# ModemAdapter.net
KiCad netlist of a schematic drawn in EAGLE
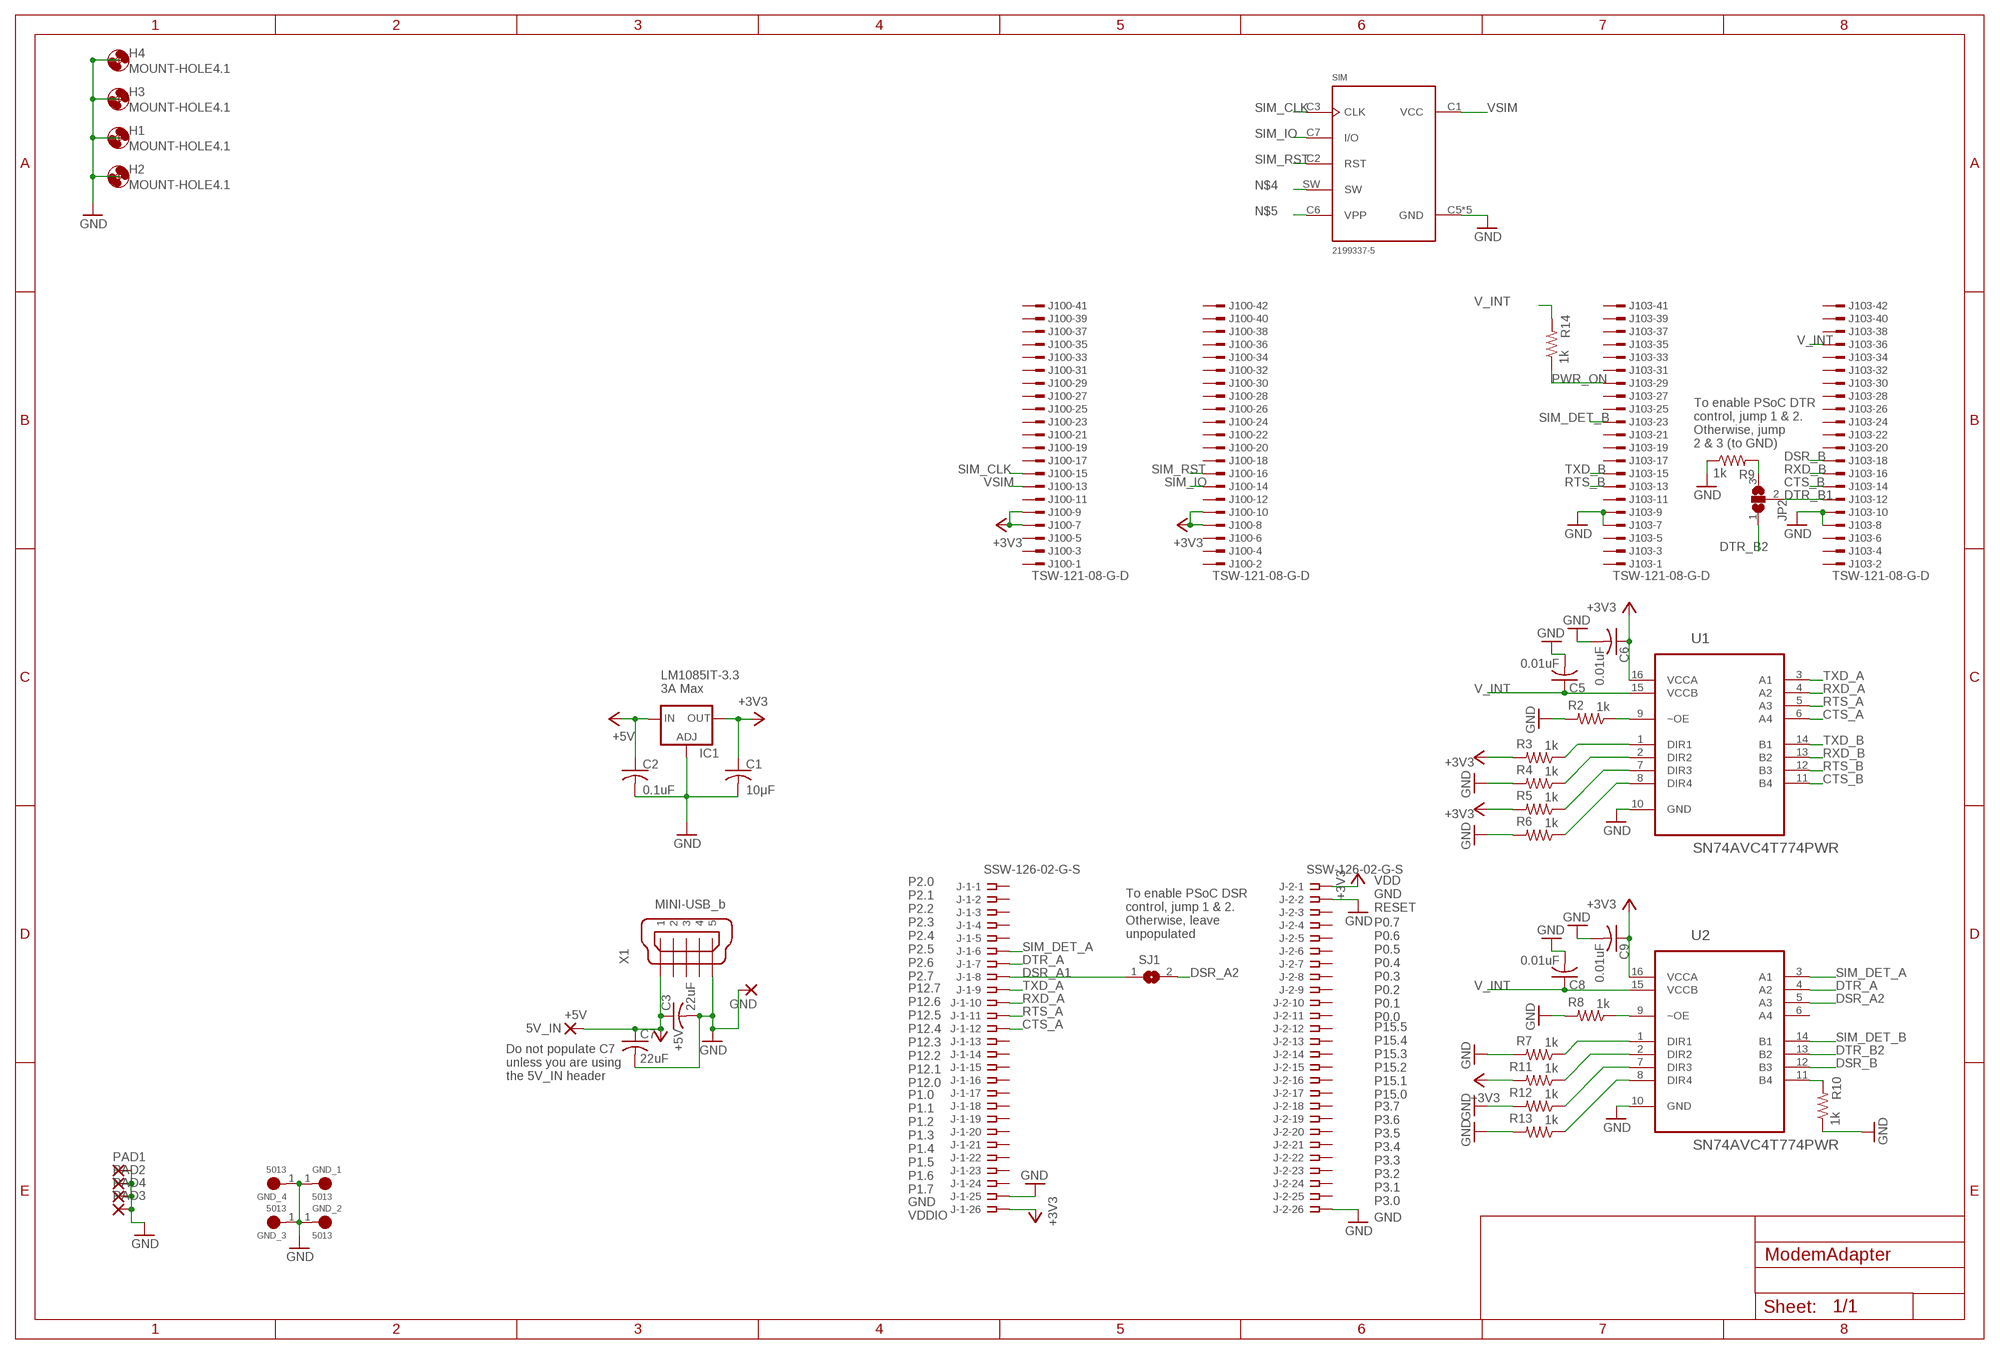
[diagram p0: schematic, sheet 1]

(export (version "E")
  (design (tool "Eeschema 10.0.6"))
  (components
    (comp (ref "+5V")
      (value "5V_IN")
      (footprint "eagle-import:3,17_1,1")
      (libsource (lib "eagle-import") (part "3,17/1,1"))
    )
    (comp (ref "C1")
      (value "10μF")
      (footprint "eagle-import:C050-024X044")
      (libsource (lib "eagle-import") (part "C-US050-024X044"))
    )
    (comp (ref "C2")
      (value "0.1uF")
      (footprint "eagle-import:C050-024X044")
      (libsource (lib "eagle-import") (part "C-US050-024X044"))
    )
    (comp (ref "C3")
      (value "22uF")
      (footprint "eagle-import:C050-024X044")
      (libsource (lib "eagle-import") (part "C-US050-024X044"))
    )
    (comp (ref "C5")
      (value "0.01uF")
      (footprint "eagle-import:C050-024X044")
      (libsource (lib "eagle-import") (part "C-US050-024X044"))
    )
    (comp (ref "C6")
      (value "0.01uF")
      (footprint "eagle-import:C050-024X044")
      (libsource (lib "eagle-import") (part "C-US050-024X044"))
    )
    (comp (ref "C7")
      (value "22uF")
      (footprint "eagle-import:C050-024X044")
      (libsource (lib "eagle-import") (part "C-US050-024X044"))
    )
    (comp (ref "C8")
      (value "0.01uF")
      (footprint "eagle-import:C050-024X044")
      (libsource (lib "eagle-import") (part "C-US050-024X044"))
    )
    (comp (ref "C9")
      (value "0.01uF")
      (footprint "eagle-import:C050-024X044")
      (libsource (lib "eagle-import") (part "C-US050-024X044"))
    )
    (comp (ref "GND")
      (value "3,17/1,1")
      (footprint "eagle-import:3,17_1,1")
      (libsource (lib "eagle-import") (part "3,17/1,1"))
    )
    (comp (ref "GND_1")
      (value "5013")
      (footprint "eagle-import:TESTPOINT_5013")
      (fields (field (name "MF") "Keystone Electronics"))
      (libsource (lib "eagle-import") (part "5013"))
    )
    (comp (ref "GND_2")
      (value "5013")
      (footprint "eagle-import:TESTPOINT_5013")
      (fields (field (name "MF") "Keystone Electronics"))
      (libsource (lib "eagle-import") (part "5013"))
    )
    (comp (ref "GND_3")
      (value "5013")
      (footprint "eagle-import:TESTPOINT_5013")
      (fields (field (name "MF") "Keystone Electronics"))
      (libsource (lib "eagle-import") (part "5013"))
    )
    (comp (ref "GND_4")
      (value "5013")
      (footprint "eagle-import:TESTPOINT_5013")
      (fields (field (name "MF") "Keystone Electronics"))
      (libsource (lib "eagle-import") (part "5013"))
    )
    (comp (ref "H1")
      (value "MOUNT-HOLE4.1")
      (footprint "eagle-import:4,1")
      (libsource (lib "eagle-import") (part "MOUNT-HOLE4.1"))
    )
    (comp (ref "H2")
      (value "MOUNT-HOLE4.1")
      (footprint "eagle-import:4,1")
      (libsource (lib "eagle-import") (part "MOUNT-HOLE4.1"))
    )
    (comp (ref "H3")
      (value "MOUNT-HOLE4.1")
      (footprint "eagle-import:4,1")
      (libsource (lib "eagle-import") (part "MOUNT-HOLE4.1"))
    )
    (comp (ref "H4")
      (value "MOUNT-HOLE4.1")
      (footprint "eagle-import:4,1")
      (libsource (lib "eagle-import") (part "MOUNT-HOLE4.1"))
    )
    (comp (ref "IC1")
      (value "LD117AV33")
      (footprint "eagle-import:TO220L1")
      (libsource (lib "eagle-import") (part "LD117A?V33"))
    )
    (comp (ref "J-1")
      (value "SSW-126-02-G-S")
      (footprint "eagle-import:SSW-126-02-G-S")
      (fields (field (name "MF") "Samtec Inc."))
      (libsource (lib "eagle-import") (part "SSW-126-02-G-S"))
    )
    (comp (ref "J-2")
      (value "SSW-126-02-G-S")
      (footprint "eagle-import:SSW-126-02-G-S")
      (fields (field (name "MF") "Samtec Inc."))
      (libsource (lib "eagle-import") (part "SSW-126-02-G-S"))
    )
    (comp (ref "J100")
      (value "TSW-121-08-G-D")
      (footprint "eagle-import:TSW-121-XX-G-D")
      (fields (field (name "MF") "Samtec Inc.") (field (name "MPN") "TSW-121-07-G-D"))
      (libsource (lib "eagle-import") (part "TSW-121--G-D08"))
    )
    (comp (ref "J103")
      (value "TSW-121-08-G-D")
      (footprint "eagle-import:TSW-121-XX-G-D")
      (fields (field (name "MF") "Samtec Inc.") (field (name "MPN") "TSW-121-07-G-D"))
      (libsource (lib "eagle-import") (part "TSW-121--G-D08"))
    )
    (comp (ref "JP2")
      (value "SJ2W")
      (footprint "eagle-import:SJ_2")
      (libsource (lib "eagle-import") (part "SJ2W"))
    )
    (comp (ref "PAD1")
      (value "SMD2")
      (footprint "eagle-import:SMD1,27-2,54")
      (libsource (lib "eagle-import") (part "SMD2"))
    )
    (comp (ref "PAD2")
      (value "SMD2")
      (footprint "eagle-import:SMD1,27-2,54")
      (libsource (lib "eagle-import") (part "SMD2"))
    )
    (comp (ref "PAD3")
      (value "SMD2")
      (footprint "eagle-import:SMD1,27-2,54")
      (libsource (lib "eagle-import") (part "SMD2"))
    )
    (comp (ref "PAD4")
      (value "SMD2")
      (footprint "eagle-import:SMD1,27-2,54")
      (libsource (lib "eagle-import") (part "SMD2"))
    )
    (comp (ref "R2")
      (value "1k")
      (footprint "eagle-import:0204_7")
      (libsource (lib "eagle-import") (part "R-US_0204/7"))
    )
    (comp (ref "R3")
      (value "1k")
      (footprint "eagle-import:0204_7")
      (libsource (lib "eagle-import") (part "R-US_0204/7"))
    )
    (comp (ref "R4")
      (value "1k")
      (footprint "eagle-import:0204_7")
      (libsource (lib "eagle-import") (part "R-US_0204/7"))
    )
    (comp (ref "R5")
      (value "1k")
      (footprint "eagle-import:0204_7")
      (libsource (lib "eagle-import") (part "R-US_0204/7"))
    )
    (comp (ref "R6")
      (value "1k")
      (footprint "eagle-import:0204_7")
      (libsource (lib "eagle-import") (part "R-US_0204/7"))
    )
    (comp (ref "R7")
      (value "1k")
      (footprint "eagle-import:0204_7")
      (libsource (lib "eagle-import") (part "R-US_0204/7"))
    )
    (comp (ref "R8")
      (value "1k")
      (footprint "eagle-import:0204_7")
      (libsource (lib "eagle-import") (part "R-US_0204/7"))
    )
    (comp (ref "R9")
      (value "1k")
      (footprint "eagle-import:0204_7")
      (libsource (lib "eagle-import") (part "R-US_0204/7"))
    )
    (comp (ref "R10")
      (value "1k")
      (footprint "eagle-import:0204_7")
      (libsource (lib "eagle-import") (part "R-US_0204/7"))
    )
    (comp (ref "R11")
      (value "1k")
      (footprint "eagle-import:0204_7")
      (libsource (lib "eagle-import") (part "R-US_0204/7"))
    )
    (comp (ref "R12")
      (value "1k")
      (footprint "eagle-import:0204_7")
      (libsource (lib "eagle-import") (part "R-US_0204/7"))
    )
    (comp (ref "R13")
      (value "1k")
      (footprint "eagle-import:0204_7")
      (libsource (lib "eagle-import") (part "R-US_0204/7"))
    )
    (comp (ref "R14")
      (value "1k")
      (footprint "eagle-import:0204_7")
      (libsource (lib "eagle-import") (part "R-US_0204/7"))
    )
    (comp (ref "SIM")
      (value "2199337-5")
      (footprint "eagle-import:TE_2199337-5")
      (fields (field (name "DIGI-KEY_PART_NUMBER") "A125065CT-ND") (field (name "MF") "TE Connectivity"))
      (libsource (lib "eagle-import") (part "2199337-5"))
    )
    (comp (ref "SJ1") (value "SJ") (footprint "eagle-import:SJ") (libsource (lib "eagle-import") (part "SJ")))
    (comp (ref "U1")
      (value "SN74AVC4T774PWR")
      (footprint "eagle-import:SOP65P640X120-16N")
      (fields (field (name "DIGI-KEY_PART_NUMBER") "296-24739-1-ND") (field (name "MF") "Texas Instruments"))
      (libsource (lib "eagle-import") (part "SN74AVC4T774PWR"))
    )
    (comp (ref "U2")
      (value "SN74AVC4T774PWR")
      (footprint "eagle-import:SOP65P640X120-16N")
      (fields (field (name "DIGI-KEY_PART_NUMBER") "296-24739-1-ND") (field (name "MF") "Texas Instruments"))
      (libsource (lib "eagle-import") (part "SN74AVC4T774PWR"))
    )
    (comp (ref "X1")
      (value "MINI-USB_b")
      (footprint "eagle-import:32005-601")
      (libsource (lib "eagle-import") (part "MINI-USB_SHIELD5P2-32005-601"))
    )
  )
  (nets
    (net (code "1") (name "+3V3") (class "Default")
      (node (ref "C1") (pin "1") (pinfunction "1_1") (pintype "passive"))
      (node (ref "C6") (pin "1") (pinfunction "1_1") (pintype "passive"))
      (node (ref "C9") (pin "1") (pinfunction "1_1") (pintype "passive"))
      (node (ref "IC1") (pin "2") (pinfunction "OUT_2") (pintype "passive"))
      (node (ref "J-1") (pin "26") (pinfunction "1_26") (pintype "passive"))
      (node (ref "J-2") (pin "1") (pinfunction "1_1") (pintype "passive"))
      (node (ref "J100") (pin "10") (pinfunction "1_10") (pintype "passive"))
      (node (ref "J100") (pin "7") (pinfunction "1_7") (pintype "passive"))
      (node (ref "J100") (pin "8") (pinfunction "1_8") (pintype "passive"))
      (node (ref "J100") (pin "9") (pinfunction "1_9") (pintype "passive"))
      (node (ref "R11") (pin "2") (pinfunction "2_2") (pintype "passive"))
      (node (ref "R3") (pin "2") (pinfunction "2_2") (pintype "passive"))
      (node (ref "R5") (pin "2") (pinfunction "2_2") (pintype "passive"))
      (node (ref "U1") (pin "16") (pinfunction "VCCA_16") (pintype "power_in"))
      (node (ref "U2") (pin "16") (pinfunction "VCCA_16") (pintype "power_in"))
    )
    (net (code "2") (name "+5V") (class "Default")
      (node (ref "+5V") (pin "1") (pinfunction "P_1") (pintype "passive"))
      (node (ref "C2") (pin "1") (pinfunction "1_1") (pintype "passive"))
      (node (ref "C3") (pin "1") (pinfunction "1_1") (pintype "passive"))
      (node (ref "C7") (pin "1") (pinfunction "1_1") (pintype "passive"))
      (node (ref "IC1") (pin "3") (pinfunction "IN_3") (pintype "input"))
      (node (ref "X1") (pin "1") (pinfunction "1_1") (pintype "passive"))
    )
    (net (code "3") (name "/CTS_A") (class "Default")
      (node (ref "J-1") (pin "12") (pinfunction "1_12") (pintype "passive"))
      (node (ref "U1") (pin "6") (pinfunction "A4_6") (pintype "bidirectional"))
    )
    (net (code "4") (name "/CTS_B") (class "Default")
      (node (ref "J103") (pin "14") (pinfunction "1_14") (pintype "passive"))
      (node (ref "U1") (pin "11") (pinfunction "B4_11") (pintype "bidirectional"))
    )
    (net (code "5") (name "/DSR_A1") (class "Default")
      (node (ref "J-1") (pin "8") (pinfunction "1_8") (pintype "passive"))
      (node (ref "SJ1") (pin "1") (pinfunction "1_1") (pintype "passive"))
    )
    (net (code "6") (name "/DSR_A2") (class "Default")
      (node (ref "SJ1") (pin "2") (pinfunction "2_2") (pintype "passive"))
      (node (ref "U2") (pin "5") (pinfunction "A3_5") (pintype "bidirectional"))
    )
    (net (code "7") (name "/DSR_B") (class "Default")
      (node (ref "J103") (pin "18") (pinfunction "1_18") (pintype "passive"))
      (node (ref "U2") (pin "12") (pinfunction "B3_12") (pintype "bidirectional"))
    )
    (net (code "8") (name "/DTR_A") (class "Default")
      (node (ref "J-1") (pin "7") (pinfunction "1_7") (pintype "passive"))
      (node (ref "U2") (pin "4") (pinfunction "A2_4") (pintype "bidirectional"))
    )
    (net (code "9") (name "/DTR_B1") (class "Default")
      (node (ref "J103") (pin "12") (pinfunction "1_12") (pintype "passive"))
      (node (ref "JP2") (pin "2") (pinfunction "2_2") (pintype "passive"))
    )
    (net (code "10") (name "/DTR_B2") (class "Default")
      (node (ref "JP2") (pin "1") (pinfunction "1_1") (pintype "passive"))
      (node (ref "U2") (pin "13") (pinfunction "B2_13") (pintype "bidirectional"))
    )
    (net (code "11") (name "/N$4") (class "Default")
      (node (ref "SIM") (pin "SW") (pinfunction "SW_SW") (pintype "passive"))
    )
    (net (code "12") (name "/N$5") (class "Default")
      (node (ref "SIM") (pin "C6") (pinfunction "VPP_C6") (pintype "passive"))
    )
    (net (code "13") (name "/PWR_ON") (class "Default")
      (node (ref "J103") (pin "29") (pinfunction "1_29") (pintype "passive"))
      (node (ref "R14") (pin "1") (pinfunction "1_1") (pintype "passive"))
    )
    (net (code "14") (name "/RTS_A") (class "Default")
      (node (ref "J-1") (pin "11") (pinfunction "1_11") (pintype "passive"))
      (node (ref "U1") (pin "5") (pinfunction "A3_5") (pintype "bidirectional"))
    )
    (net (code "15") (name "/RTS_B") (class "Default")
      (node (ref "J103") (pin "13") (pinfunction "1_13") (pintype "passive"))
      (node (ref "U1") (pin "12") (pinfunction "B3_12") (pintype "bidirectional"))
    )
    (net (code "16") (name "/RXD_A") (class "Default")
      (node (ref "J-1") (pin "10") (pinfunction "1_10") (pintype "passive"))
      (node (ref "U1") (pin "4") (pinfunction "A2_4") (pintype "bidirectional"))
    )
    (net (code "17") (name "/RXD_B") (class "Default")
      (node (ref "J103") (pin "16") (pinfunction "1_16") (pintype "passive"))
      (node (ref "U1") (pin "13") (pinfunction "B2_13") (pintype "bidirectional"))
    )
    (net (code "18") (name "/SIM_CLK") (class "Default")
      (node (ref "J100") (pin "15") (pinfunction "1_15") (pintype "passive"))
      (node (ref "SIM") (pin "C3") (pinfunction "CLK_C3") (pintype "input"))
    )
    (net (code "19") (name "/SIM_DET_A") (class "Default")
      (node (ref "J-1") (pin "6") (pinfunction "1_6") (pintype "passive"))
      (node (ref "U2") (pin "3") (pinfunction "A1_3") (pintype "bidirectional"))
    )
    (net (code "20") (name "/SIM_DET_B") (class "Default")
      (node (ref "J103") (pin "23") (pinfunction "1_23") (pintype "passive"))
      (node (ref "U2") (pin "14") (pinfunction "B1_14") (pintype "bidirectional"))
    )
    (net (code "21") (name "/SIM_IO") (class "Default")
      (node (ref "J100") (pin "14") (pinfunction "1_14") (pintype "passive"))
      (node (ref "SIM") (pin "C7") (pinfunction "I/O_C7") (pintype "bidirectional"))
    )
    (net (code "22") (name "/SIM_RST") (class "Default")
      (node (ref "J100") (pin "16") (pinfunction "1_16") (pintype "passive"))
      (node (ref "SIM") (pin "C2") (pinfunction "RST_C2") (pintype "passive"))
    )
    (net (code "23") (name "/TXD_A") (class "Default")
      (node (ref "J-1") (pin "9") (pinfunction "1_9") (pintype "passive"))
      (node (ref "U1") (pin "3") (pinfunction "A1_3") (pintype "bidirectional"))
    )
    (net (code "24") (name "/TXD_B") (class "Default")
      (node (ref "J103") (pin "15") (pinfunction "1_15") (pintype "passive"))
      (node (ref "U1") (pin "14") (pinfunction "B1_14") (pintype "bidirectional"))
    )
    (net (code "25") (name "/VSIM") (class "Default")
      (node (ref "J100") (pin "13") (pinfunction "1_13") (pintype "passive"))
      (node (ref "SIM") (pin "C1") (pinfunction "VCC_C1") (pintype "power_in"))
    )
    (net (code "26") (name "/V_INT") (class "Default")
      (node (ref "C5") (pin "1") (pinfunction "1_1") (pintype "passive"))
      (node (ref "C8") (pin "1") (pinfunction "1_1") (pintype "passive"))
      (node (ref "J103") (pin "36") (pinfunction "1_36") (pintype "passive"))
      (node (ref "R14") (pin "2") (pinfunction "2_2") (pintype "passive"))
      (node (ref "U1") (pin "15") (pinfunction "VCCB_15") (pintype "power_in"))
      (node (ref "U2") (pin "15") (pinfunction "VCCB_15") (pintype "power_in"))
    )
    (net (code "27") (name "GND") (class "Default")
      (node (ref "C1") (pin "2") (pinfunction "2_2") (pintype "passive"))
      (node (ref "C2") (pin "2") (pinfunction "2_2") (pintype "passive"))
      (node (ref "C3") (pin "2") (pinfunction "2_2") (pintype "passive"))
      (node (ref "C5") (pin "2") (pinfunction "2_2") (pintype "passive"))
      (node (ref "C6") (pin "2") (pinfunction "2_2") (pintype "passive"))
      (node (ref "C7") (pin "2") (pinfunction "2_2") (pintype "passive"))
      (node (ref "C8") (pin "2") (pinfunction "2_2") (pintype "passive"))
      (node (ref "C9") (pin "2") (pinfunction "2_2") (pintype "passive"))
      (node (ref "GND") (pin "1") (pinfunction "P_1") (pintype "passive"))
      (node (ref "GND_1") (pin "1") (pinfunction "TP_1") (pintype "passive"))
      (node (ref "GND_2") (pin "1") (pinfunction "TP_1") (pintype "passive"))
      (node (ref "GND_3") (pin "1") (pinfunction "TP_1") (pintype "passive"))
      (node (ref "GND_4") (pin "1") (pinfunction "TP_1") (pintype "passive"))
      (node (ref "IC1") (pin "1") (pinfunction "ADJ_1") (pintype "input"))
      (node (ref "J-1") (pin "25") (pinfunction "1_25") (pintype "passive"))
      (node (ref "J-2") (pin "2") (pinfunction "1_2") (pintype "passive"))
      (node (ref "J-2") (pin "26") (pinfunction "1_26") (pintype "passive"))
      (node (ref "J103") (pin "10") (pinfunction "1_10") (pintype "passive"))
      (node (ref "J103") (pin "7") (pinfunction "1_7") (pintype "passive"))
      (node (ref "J103") (pin "8") (pinfunction "1_8") (pintype "passive"))
      (node (ref "J103") (pin "9") (pinfunction "1_9") (pintype "passive"))
      (node (ref "PAD1") (pin "1") (pinfunction "P_1") (pintype "passive"))
      (node (ref "PAD2") (pin "1") (pinfunction "P_1") (pintype "passive"))
      (node (ref "PAD3") (pin "1") (pinfunction "P_1") (pintype "passive"))
      (node (ref "PAD4") (pin "1") (pinfunction "P_1") (pintype "passive"))
      (node (ref "R10") (pin "1") (pinfunction "1_1") (pintype "passive"))
      (node (ref "R12") (pin "2") (pinfunction "2_2") (pintype "passive"))
      (node (ref "R13") (pin "2") (pinfunction "2_2") (pintype "passive"))
      (node (ref "R2") (pin "2") (pinfunction "2_2") (pintype "passive"))
      (node (ref "R4") (pin "2") (pinfunction "2_2") (pintype "passive"))
      (node (ref "R6") (pin "2") (pinfunction "2_2") (pintype "passive"))
      (node (ref "R7") (pin "2") (pinfunction "2_2") (pintype "passive"))
      (node (ref "R8") (pin "2") (pinfunction "2_2") (pintype "passive"))
      (node (ref "R9") (pin "1") (pinfunction "1_1") (pintype "passive"))
      (node (ref "SIM") (pin "C5") (pinfunction "GND_C5") (pintype "power_in"))
      (node (ref "SIM") (pin "G1") (pinfunction "GND_G1") (pintype "power_in"))
      (node (ref "SIM") (pin "G2") (pinfunction "GND_G2") (pintype "power_in"))
      (node (ref "SIM") (pin "G3") (pinfunction "GND_G3") (pintype "power_in"))
      (node (ref "SIM") (pin "G4") (pinfunction "GND_G4") (pintype "power_in"))
      (node (ref "U1") (pin "10") (pinfunction "GND_10") (pintype "passive"))
      (node (ref "U2") (pin "10") (pinfunction "GND_10") (pintype "passive"))
      (node (ref "X1") (pin "5") (pinfunction "5_5") (pintype "passive"))
    )
    (net (code "28") (name "Net-(JP2-Pad3)") (class "Default")
      (node (ref "JP2") (pin "3") (pinfunction "3_3") (pintype "passive"))
      (node (ref "R9") (pin "2") (pinfunction "2_2") (pintype "passive"))
    )
    (net (code "29") (name "Net-(U1-DIR1)") (class "Default")
      (node (ref "R3") (pin "1") (pinfunction "1_1") (pintype "passive"))
      (node (ref "U1") (pin "1") (pinfunction "DIR1_1") (pintype "input"))
    )
    (net (code "30") (name "Net-(U1-DIR2)") (class "Default")
      (node (ref "R4") (pin "1") (pinfunction "1_1") (pintype "passive"))
      (node (ref "U1") (pin "2") (pinfunction "DIR2_2") (pintype "input"))
    )
    (net (code "31") (name "Net-(U1-DIR3)") (class "Default")
      (node (ref "R5") (pin "1") (pinfunction "1_1") (pintype "passive"))
      (node (ref "U1") (pin "7") (pinfunction "DIR3_7") (pintype "input"))
    )
    (net (code "32") (name "Net-(U1-DIR4)") (class "Default")
      (node (ref "R6") (pin "1") (pinfunction "1_1") (pintype "passive"))
      (node (ref "U1") (pin "8") (pinfunction "DIR4_8") (pintype "input"))
    )
    (net (code "33") (name "Net-(U1-~{OE})") (class "Default")
      (node (ref "R2") (pin "1") (pinfunction "1_1") (pintype "passive"))
      (node (ref "U1") (pin "9") (pinfunction "~{OE}_9") (pintype "input"))
    )
    (net (code "34") (name "Net-(U2-B4)") (class "Default")
      (node (ref "R10") (pin "2") (pinfunction "2_2") (pintype "passive"))
      (node (ref "U2") (pin "11") (pinfunction "B4_11") (pintype "bidirectional"))
    )
    (net (code "35") (name "Net-(U2-DIR1)") (class "Default")
      (node (ref "R7") (pin "1") (pinfunction "1_1") (pintype "passive"))
      (node (ref "U2") (pin "1") (pinfunction "DIR1_1") (pintype "input"))
    )
    (net (code "36") (name "Net-(U2-DIR2)") (class "Default")
      (node (ref "R11") (pin "1") (pinfunction "1_1") (pintype "passive"))
      (node (ref "U2") (pin "2") (pinfunction "DIR2_2") (pintype "input"))
    )
    (net (code "37") (name "Net-(U2-DIR3)") (class "Default")
      (node (ref "R12") (pin "1") (pinfunction "1_1") (pintype "passive"))
      (node (ref "U2") (pin "7") (pinfunction "DIR3_7") (pintype "input"))
    )
    (net (code "38") (name "Net-(U2-DIR4)") (class "Default")
      (node (ref "R13") (pin "1") (pinfunction "1_1") (pintype "passive"))
      (node (ref "U2") (pin "8") (pinfunction "DIR4_8") (pintype "input"))
    )
    (net (code "39") (name "Net-(U2-~{OE})") (class "Default")
      (node (ref "R8") (pin "1") (pinfunction "1_1") (pintype "passive"))
      (node (ref "U2") (pin "9") (pinfunction "~{OE}_9") (pintype "input"))
    )
    (net (code "40") (name "unconnected-(J-1-Pad1)") (class "Default")
      (node (ref "J-1") (pin "1") (pinfunction "1_1") (pintype "passive"))
    )
    (net (code "41") (name "unconnected-(J-1E-1-Pad13)") (class "Default")
      (node (ref "J-1") (pin "13") (pinfunction "1_13") (pintype "passive"))
    )
    (net (code "42") (name "unconnected-(J-1F-1-Pad14)") (class "Default")
      (node (ref "J-1") (pin "14") (pinfunction "1_14") (pintype "passive"))
    )
    (net (code "43") (name "unconnected-(J-1G-1-Pad15)") (class "Default")
      (node (ref "J-1") (pin "15") (pinfunction "1_15") (pintype "passive"))
    )
    (net (code "44") (name "unconnected-(J-1H-1-Pad16)") (class "Default")
      (node (ref "J-1") (pin "16") (pinfunction "1_16") (pintype "passive"))
    )
    (net (code "45") (name "unconnected-(J-1I-1-Pad17)") (class "Default")
      (node (ref "J-1") (pin "17") (pinfunction "1_17") (pintype "passive"))
    )
    (net (code "46") (name "unconnected-(J-1J-1-Pad18)") (class "Default")
      (node (ref "J-1") (pin "18") (pinfunction "1_18") (pintype "passive"))
    )
    (net (code "47") (name "unconnected-(J-1K-1-Pad19)") (class "Default")
      (node (ref "J-1") (pin "19") (pinfunction "1_19") (pintype "passive"))
    )
    (net (code "48") (name "unconnected-(J-1L-1-Pad2)") (class "Default")
      (node (ref "J-1") (pin "2") (pinfunction "1_2") (pintype "passive"))
    )
    (net (code "49") (name "unconnected-(J-1M-1-Pad20)") (class "Default")
      (node (ref "J-1") (pin "20") (pinfunction "1_20") (pintype "passive"))
    )
    (net (code "50") (name "unconnected-(J-1N-1-Pad21)") (class "Default")
      (node (ref "J-1") (pin "21") (pinfunction "1_21") (pintype "passive"))
    )
    (net (code "51") (name "unconnected-(J-1O-1-Pad22)") (class "Default")
      (node (ref "J-1") (pin "22") (pinfunction "1_22") (pintype "passive"))
    )
    (net (code "52") (name "unconnected-(J-1P-1-Pad23)") (class "Default")
      (node (ref "J-1") (pin "23") (pinfunction "1_23") (pintype "passive"))
    )
    (net (code "53") (name "unconnected-(J-1Q-1-Pad24)") (class "Default")
      (node (ref "J-1") (pin "24") (pinfunction "1_24") (pintype "passive"))
    )
    (net (code "54") (name "unconnected-(J-1T-1-Pad3)") (class "Default")
      (node (ref "J-1") (pin "3") (pinfunction "1_3") (pintype "passive"))
    )
    (net (code "55") (name "unconnected-(J-1U-1-Pad4)") (class "Default")
      (node (ref "J-1") (pin "4") (pinfunction "1_4") (pintype "passive"))
    )
    (net (code "56") (name "unconnected-(J-1V-1-Pad5)") (class "Default")
      (node (ref "J-1") (pin "5") (pinfunction "1_5") (pintype "passive"))
    )
    (net (code "57") (name "unconnected-(J-2B-1-Pad10)") (class "Default")
      (node (ref "J-2") (pin "10") (pinfunction "1_10") (pintype "passive"))
    )
    (net (code "58") (name "unconnected-(J-2C-1-Pad11)") (class "Default")
      (node (ref "J-2") (pin "11") (pinfunction "1_11") (pintype "passive"))
    )
    (net (code "59") (name "unconnected-(J-2D-1-Pad12)") (class "Default")
      (node (ref "J-2") (pin "12") (pinfunction "1_12") (pintype "passive"))
    )
    (net (code "60") (name "unconnected-(J-2E-1-Pad13)") (class "Default")
      (node (ref "J-2") (pin "13") (pinfunction "1_13") (pintype "passive"))
    )
    (net (code "61") (name "unconnected-(J-2F-1-Pad14)") (class "Default")
      (node (ref "J-2") (pin "14") (pinfunction "1_14") (pintype "passive"))
    )
    (net (code "62") (name "unconnected-(J-2G-1-Pad15)") (class "Default")
      (node (ref "J-2") (pin "15") (pinfunction "1_15") (pintype "passive"))
    )
    (net (code "63") (name "unconnected-(J-2H-1-Pad16)") (class "Default")
      (node (ref "J-2") (pin "16") (pinfunction "1_16") (pintype "passive"))
    )
    (net (code "64") (name "unconnected-(J-2I-1-Pad17)") (class "Default")
      (node (ref "J-2") (pin "17") (pinfunction "1_17") (pintype "passive"))
    )
    (net (code "65") (name "unconnected-(J-2J-1-Pad18)") (class "Default")
      (node (ref "J-2") (pin "18") (pinfunction "1_18") (pintype "passive"))
    )
    (net (code "66") (name "unconnected-(J-2K-1-Pad19)") (class "Default")
      (node (ref "J-2") (pin "19") (pinfunction "1_19") (pintype "passive"))
    )
    (net (code "67") (name "unconnected-(J-2M-1-Pad20)") (class "Default")
      (node (ref "J-2") (pin "20") (pinfunction "1_20") (pintype "passive"))
    )
    (net (code "68") (name "unconnected-(J-2N-1-Pad21)") (class "Default")
      (node (ref "J-2") (pin "21") (pinfunction "1_21") (pintype "passive"))
    )
    (net (code "69") (name "unconnected-(J-2O-1-Pad22)") (class "Default")
      (node (ref "J-2") (pin "22") (pinfunction "1_22") (pintype "passive"))
    )
    (net (code "70") (name "unconnected-(J-2P-1-Pad23)") (class "Default")
      (node (ref "J-2") (pin "23") (pinfunction "1_23") (pintype "passive"))
    )
    (net (code "71") (name "unconnected-(J-2Q-1-Pad24)") (class "Default")
      (node (ref "J-2") (pin "24") (pinfunction "1_24") (pintype "passive"))
    )
    (net (code "72") (name "unconnected-(J-2R-1-Pad25)") (class "Default")
      (node (ref "J-2") (pin "25") (pinfunction "1_25") (pintype "passive"))
    )
    (net (code "73") (name "unconnected-(J-2T-1-Pad3)") (class "Default")
      (node (ref "J-2") (pin "3") (pinfunction "1_3") (pintype "passive"))
    )
    (net (code "74") (name "unconnected-(J-2U-1-Pad4)") (class "Default")
      (node (ref "J-2") (pin "4") (pinfunction "1_4") (pintype "passive"))
    )
    (net (code "75") (name "unconnected-(J-2V-1-Pad5)") (class "Default")
      (node (ref "J-2") (pin "5") (pinfunction "1_5") (pintype "passive"))
    )
    (net (code "76") (name "unconnected-(J-2W-1-Pad6)") (class "Default")
      (node (ref "J-2") (pin "6") (pinfunction "1_6") (pintype "passive"))
    )
    (net (code "77") (name "unconnected-(J-2X-1-Pad7)") (class "Default")
      (node (ref "J-2") (pin "7") (pinfunction "1_7") (pintype "passive"))
    )
    (net (code "78") (name "unconnected-(J-2Y-1-Pad8)") (class "Default")
      (node (ref "J-2") (pin "8") (pinfunction "1_8") (pintype "passive"))
    )
    (net (code "79") (name "unconnected-(J-2Z-1-Pad9)") (class "Default")
      (node (ref "J-2") (pin "9") (pinfunction "1_9") (pintype "passive"))
    )
    (net (code "80") (name "unconnected-(J100-Pad1)") (class "Default")
      (node (ref "J100") (pin "1") (pinfunction "1_1") (pintype "passive"))
    )
    (net (code "81") (name "unconnected-(J100AA-1-Pad33)") (class "Default")
      (node (ref "J100") (pin "33") (pinfunction "1_33") (pintype "passive"))
    )
    (net (code "82") (name "unconnected-(J100AB-1-Pad34)") (class "Default")
      (node (ref "J100") (pin "34") (pinfunction "1_34") (pintype "passive"))
    )
    (net (code "83") (name "unconnected-(J100AC-1-Pad35)") (class "Default")
      (node (ref "J100") (pin "35") (pinfunction "1_35") (pintype "passive"))
    )
    (net (code "84") (name "unconnected-(J100AD-1-Pad36)") (class "Default")
      (node (ref "J100") (pin "36") (pinfunction "1_36") (pintype "passive"))
    )
    (net (code "85") (name "unconnected-(J100AE-1-Pad37)") (class "Default")
      (node (ref "J100") (pin "37") (pinfunction "1_37") (pintype "passive"))
    )
    (net (code "86") (name "unconnected-(J100AF-1-Pad38)") (class "Default")
      (node (ref "J100") (pin "38") (pinfunction "1_38") (pintype "passive"))
    )
    (net (code "87") (name "unconnected-(J100AG-1-Pad39)") (class "Default")
      (node (ref "J100") (pin "39") (pinfunction "1_39") (pintype "passive"))
    )
    (net (code "88") (name "unconnected-(J100AH-1-Pad4)") (class "Default")
      (node (ref "J100") (pin "4") (pinfunction "1_4") (pintype "passive"))
    )
    (net (code "89") (name "unconnected-(J100AI-1-Pad40)") (class "Default")
      (node (ref "J100") (pin "40") (pinfunction "1_40") (pintype "passive"))
    )
    (net (code "90") (name "unconnected-(J100AJ-1-Pad41)") (class "Default")
      (node (ref "J100") (pin "41") (pinfunction "1_41") (pintype "passive"))
    )
    (net (code "91") (name "unconnected-(J100AK-1-Pad42)") (class "Default")
      (node (ref "J100") (pin "42") (pinfunction "1_42") (pintype "passive"))
    )
    (net (code "92") (name "unconnected-(J100AL-1-Pad5)") (class "Default")
      (node (ref "J100") (pin "5") (pinfunction "1_5") (pintype "passive"))
    )
    (net (code "93") (name "unconnected-(J100AM-1-Pad6)") (class "Default")
      (node (ref "J100") (pin "6") (pinfunction "1_6") (pintype "passive"))
    )
    (net (code "94") (name "unconnected-(J100C-1-Pad11)") (class "Default")
      (node (ref "J100") (pin "11") (pinfunction "1_11") (pintype "passive"))
    )
    (net (code "95") (name "unconnected-(J100D-1-Pad12)") (class "Default")
      (node (ref "J100") (pin "12") (pinfunction "1_12") (pintype "passive"))
    )
    (net (code "96") (name "unconnected-(J100I-1-Pad17)") (class "Default")
      (node (ref "J100") (pin "17") (pinfunction "1_17") (pintype "passive"))
    )
    (net (code "97") (name "unconnected-(J100J-1-Pad18)") (class "Default")
      (node (ref "J100") (pin "18") (pinfunction "1_18") (pintype "passive"))
    )
    (net (code "98") (name "unconnected-(J100K-1-Pad19)") (class "Default")
      (node (ref "J100") (pin "19") (pinfunction "1_19") (pintype "passive"))
    )
    (net (code "99") (name "unconnected-(J100L-1-Pad2)") (class "Default")
      (node (ref "J100") (pin "2") (pinfunction "1_2") (pintype "passive"))
    )
    (net (code "100") (name "unconnected-(J100M-1-Pad20)") (class "Default")
      (node (ref "J100") (pin "20") (pinfunction "1_20") (pintype "passive"))
    )
    (net (code "101") (name "unconnected-(J100N-1-Pad21)") (class "Default")
      (node (ref "J100") (pin "21") (pinfunction "1_21") (pintype "passive"))
    )
    (net (code "102") (name "unconnected-(J100O-1-Pad22)") (class "Default")
      (node (ref "J100") (pin "22") (pinfunction "1_22") (pintype "passive"))
    )
    (net (code "103") (name "unconnected-(J100P-1-Pad23)") (class "Default")
      (node (ref "J100") (pin "23") (pinfunction "1_23") (pintype "passive"))
    )
    (net (code "104") (name "unconnected-(J100Q-1-Pad24)") (class "Default")
      (node (ref "J100") (pin "24") (pinfunction "1_24") (pintype "passive"))
    )
    (net (code "105") (name "unconnected-(J100R-1-Pad25)") (class "Default")
      (node (ref "J100") (pin "25") (pinfunction "1_25") (pintype "passive"))
    )
    (net (code "106") (name "unconnected-(J100S-1-Pad26)") (class "Default")
      (node (ref "J100") (pin "26") (pinfunction "1_26") (pintype "passive"))
    )
    (net (code "107") (name "unconnected-(J100T-1-Pad27)") (class "Default")
      (node (ref "J100") (pin "27") (pinfunction "1_27") (pintype "passive"))
    )
    (net (code "108") (name "unconnected-(J100U-1-Pad28)") (class "Default")
      (node (ref "J100") (pin "28") (pinfunction "1_28") (pintype "passive"))
    )
    (net (code "109") (name "unconnected-(J100V-1-Pad29)") (class "Default")
      (node (ref "J100") (pin "29") (pinfunction "1_29") (pintype "passive"))
    )
    (net (code "110") (name "unconnected-(J100W-1-Pad3)") (class "Default")
      (node (ref "J100") (pin "3") (pinfunction "1_3") (pintype "passive"))
    )
    (net (code "111") (name "unconnected-(J100X-1-Pad30)") (class "Default")
      (node (ref "J100") (pin "30") (pinfunction "1_30") (pintype "passive"))
    )
    (net (code "112") (name "unconnected-(J100Y-1-Pad31)") (class "Default")
      (node (ref "J100") (pin "31") (pinfunction "1_31") (pintype "passive"))
    )
    (net (code "113") (name "unconnected-(J100Z-1-Pad32)") (class "Default")
      (node (ref "J100") (pin "32") (pinfunction "1_32") (pintype "passive"))
    )
    (net (code "114") (name "unconnected-(J103-Pad1)") (class "Default")
      (node (ref "J103") (pin "1") (pinfunction "1_1") (pintype "passive"))
    )
    (net (code "115") (name "unconnected-(J103AA-1-Pad33)") (class "Default")
      (node (ref "J103") (pin "33") (pinfunction "1_33") (pintype "passive"))
    )
    (net (code "116") (name "unconnected-(J103AB-1-Pad34)") (class "Default")
      (node (ref "J103") (pin "34") (pinfunction "1_34") (pintype "passive"))
    )
    (net (code "117") (name "unconnected-(J103AC-1-Pad35)") (class "Default")
      (node (ref "J103") (pin "35") (pinfunction "1_35") (pintype "passive"))
    )
    (net (code "118") (name "unconnected-(J103AE-1-Pad37)") (class "Default")
      (node (ref "J103") (pin "37") (pinfunction "1_37") (pintype "passive"))
    )
    (net (code "119") (name "unconnected-(J103AF-1-Pad38)") (class "Default")
      (node (ref "J103") (pin "38") (pinfunction "1_38") (pintype "passive"))
    )
    (net (code "120") (name "unconnected-(J103AG-1-Pad39)") (class "Default")
      (node (ref "J103") (pin "39") (pinfunction "1_39") (pintype "passive"))
    )
    (net (code "121") (name "unconnected-(J103AH-1-Pad4)") (class "Default")
      (node (ref "J103") (pin "4") (pinfunction "1_4") (pintype "passive"))
    )
    (net (code "122") (name "unconnected-(J103AI-1-Pad40)") (class "Default")
      (node (ref "J103") (pin "40") (pinfunction "1_40") (pintype "passive"))
    )
    (net (code "123") (name "unconnected-(J103AJ-1-Pad41)") (class "Default")
      (node (ref "J103") (pin "41") (pinfunction "1_41") (pintype "passive"))
    )
    (net (code "124") (name "unconnected-(J103AK-1-Pad42)") (class "Default")
      (node (ref "J103") (pin "42") (pinfunction "1_42") (pintype "passive"))
    )
    (net (code "125") (name "unconnected-(J103AL-1-Pad5)") (class "Default")
      (node (ref "J103") (pin "5") (pinfunction "1_5") (pintype "passive"))
    )
    (net (code "126") (name "unconnected-(J103AM-1-Pad6)") (class "Default")
      (node (ref "J103") (pin "6") (pinfunction "1_6") (pintype "passive"))
    )
    (net (code "127") (name "unconnected-(J103C-1-Pad11)") (class "Default")
      (node (ref "J103") (pin "11") (pinfunction "1_11") (pintype "passive"))
    )
    (net (code "128") (name "unconnected-(J103I-1-Pad17)") (class "Default")
      (node (ref "J103") (pin "17") (pinfunction "1_17") (pintype "passive"))
    )
    (net (code "129") (name "unconnected-(J103K-1-Pad19)") (class "Default")
      (node (ref "J103") (pin "19") (pinfunction "1_19") (pintype "passive"))
    )
    (net (code "130") (name "unconnected-(J103L-1-Pad2)") (class "Default")
      (node (ref "J103") (pin "2") (pinfunction "1_2") (pintype "passive"))
    )
    (net (code "131") (name "unconnected-(J103M-1-Pad20)") (class "Default")
      (node (ref "J103") (pin "20") (pinfunction "1_20") (pintype "passive"))
    )
    (net (code "132") (name "unconnected-(J103N-1-Pad21)") (class "Default")
      (node (ref "J103") (pin "21") (pinfunction "1_21") (pintype "passive"))
    )
    (net (code "133") (name "unconnected-(J103O-1-Pad22)") (class "Default")
      (node (ref "J103") (pin "22") (pinfunction "1_22") (pintype "passive"))
    )
    (net (code "134") (name "unconnected-(J103Q-1-Pad24)") (class "Default")
      (node (ref "J103") (pin "24") (pinfunction "1_24") (pintype "passive"))
    )
    (net (code "135") (name "unconnected-(J103R-1-Pad25)") (class "Default")
      (node (ref "J103") (pin "25") (pinfunction "1_25") (pintype "passive"))
    )
    (net (code "136") (name "unconnected-(J103S-1-Pad26)") (class "Default")
      (node (ref "J103") (pin "26") (pinfunction "1_26") (pintype "passive"))
    )
    (net (code "137") (name "unconnected-(J103T-1-Pad27)") (class "Default")
      (node (ref "J103") (pin "27") (pinfunction "1_27") (pintype "passive"))
    )
    (net (code "138") (name "unconnected-(J103U-1-Pad28)") (class "Default")
      (node (ref "J103") (pin "28") (pinfunction "1_28") (pintype "passive"))
    )
    (net (code "139") (name "unconnected-(J103W-1-Pad3)") (class "Default")
      (node (ref "J103") (pin "3") (pinfunction "1_3") (pintype "passive"))
    )
    (net (code "140") (name "unconnected-(J103X-1-Pad30)") (class "Default")
      (node (ref "J103") (pin "30") (pinfunction "1_30") (pintype "passive"))
    )
    (net (code "141") (name "unconnected-(J103Y-1-Pad31)") (class "Default")
      (node (ref "J103") (pin "31") (pinfunction "1_31") (pintype "passive"))
    )
    (net (code "142") (name "unconnected-(J103Z-1-Pad32)") (class "Default")
      (node (ref "J103") (pin "32") (pinfunction "1_32") (pintype "passive"))
    )
    (net (code "143") (name "unconnected-(U2-A4-Pad6)") (class "Default")
      (node (ref "U2") (pin "6") (pinfunction "A4_6") (pintype "bidirectional"))
    )
    (net (code "144") (name "unconnected-(X1-Pad2)") (class "Default")
      (node (ref "X1") (pin "2") (pinfunction "2_2") (pintype "passive"))
    )
    (net (code "145") (name "unconnected-(X1-Pad3)") (class "Default")
      (node (ref "X1") (pin "3") (pinfunction "3_3") (pintype "passive"))
    )
    (net (code "146") (name "unconnected-(X1-Pad4)") (class "Default")
      (node (ref "X1") (pin "4") (pinfunction "4_4") (pintype "passive"))
    )
  )
)
